# laser_driver.net
KiCad netlist of a schematic drawn in EAGLE
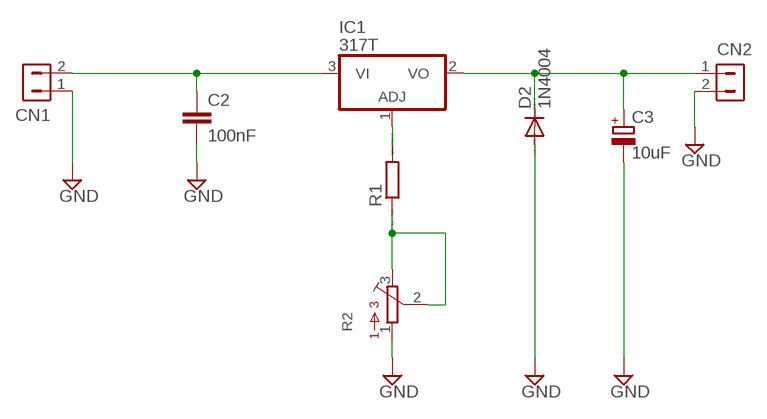
[diagram p0: schematic, sheet 1]

(export (version "E")
  (design (tool "Eeschema 10.0.6"))
  (components
    (comp (ref "C2")
      (value "100nF")
      (footprint "eagle-import:C2.5-3")
      (libsource (lib "eagle-import") (part "C2,5-3"))
    )
    (comp (ref "C3")
      (value "10uF")
      (footprint "eagle-import:E2-5")
      (libsource (lib "eagle-import") (part "CPOL-EUE2-5"))
    )
    (comp (ref "CN1")
      (value "HDR-1X2-SIP-100")
      (footprint "eagle-import:SIP-100-2V")
      (libsource (lib "eagle-import") (part "HDR-1X2-SIP-100"))
    )
    (comp (ref "CN2")
      (value "HDR-1X2-SIP-100")
      (footprint "eagle-import:SIP-100-2V")
      (libsource (lib "eagle-import") (part "HDR-1X2-SIP-100"))
    )
    (comp (ref "D2")
      (value "1N4004")
      (footprint "eagle-import:DO41-10")
      (libsource (lib "eagle-import") (part "1N4004"))
    )
    (comp (ref "IC1")
      (value "317T")
      (footprint "eagle-import:TO220H")
      (libsource (lib "eagle-import") (part "317T"))
    )
    (comp (ref "R1")
      (value "R0204/7")
      (footprint "eagle-import:0204_7")
      (libsource (lib "eagle-import") (part "R0204/7"))
    )
    (comp (ref "R2")
      (value "3386-F")
      (footprint "eagle-import:3386F")
      (libsource (lib "eagle-import") (part "3386-F"))
    )
  )
  (nets
    (net (code "1") (name "GND") (class "Default")
      (node (ref "C2") (pin "2") (pinfunction "2_2") (pintype "passive"))
      (node (ref "C3") (pin "-") (pinfunction "-_-") (pintype "passive"))
      (node (ref "CN1") (pin "1") (pinfunction "1_1") (pintype "passive"))
      (node (ref "CN2") (pin "2") (pinfunction "2_2") (pintype "passive"))
      (node (ref "D2") (pin "A") (pinfunction "A_A") (pintype "passive"))
      (node (ref "R2") (pin "1") (pinfunction "1_1") (pintype "passive"))
    )
    (net (code "2") (name "Net-(IC1-ADJ)") (class "Default")
      (node (ref "IC1") (pin "1") (pinfunction "ADJ_1") (pintype "input"))
      (node (ref "R1") (pin "2") (pinfunction "2_2") (pintype "passive"))
    )
    (net (code "3") (name "Net-(IC1-VI)") (class "Default")
      (node (ref "C2") (pin "1") (pinfunction "1_1") (pintype "passive"))
      (node (ref "CN1") (pin "2") (pinfunction "2_2") (pintype "passive"))
      (node (ref "IC1") (pin "3") (pinfunction "VI_3") (pintype "input"))
    )
    (net (code "4") (name "Net-(IC1-VO)") (class "Default")
      (node (ref "C3") (pin "+") (pinfunction "+_+") (pintype "passive"))
      (node (ref "CN2") (pin "1") (pinfunction "1_1") (pintype "passive"))
      (node (ref "D2") (pin "C") (pinfunction "C_C") (pintype "passive"))
      (node (ref "IC1") (pin "2") (pinfunction "VO_2") (pintype "passive"))
    )
    (net (code "5") (name "Net-(R1-Pad1)") (class "Default")
      (node (ref "R1") (pin "1") (pinfunction "1_1") (pintype "passive"))
      (node (ref "R2") (pin "2") (pinfunction "2_2") (pintype "passive"))
      (node (ref "R2") (pin "3") (pinfunction "3_3") (pintype "passive"))
    )
  )
)
